# USBASP_M8535.net
KiCad netlist of a schematic drawn in EAGLE
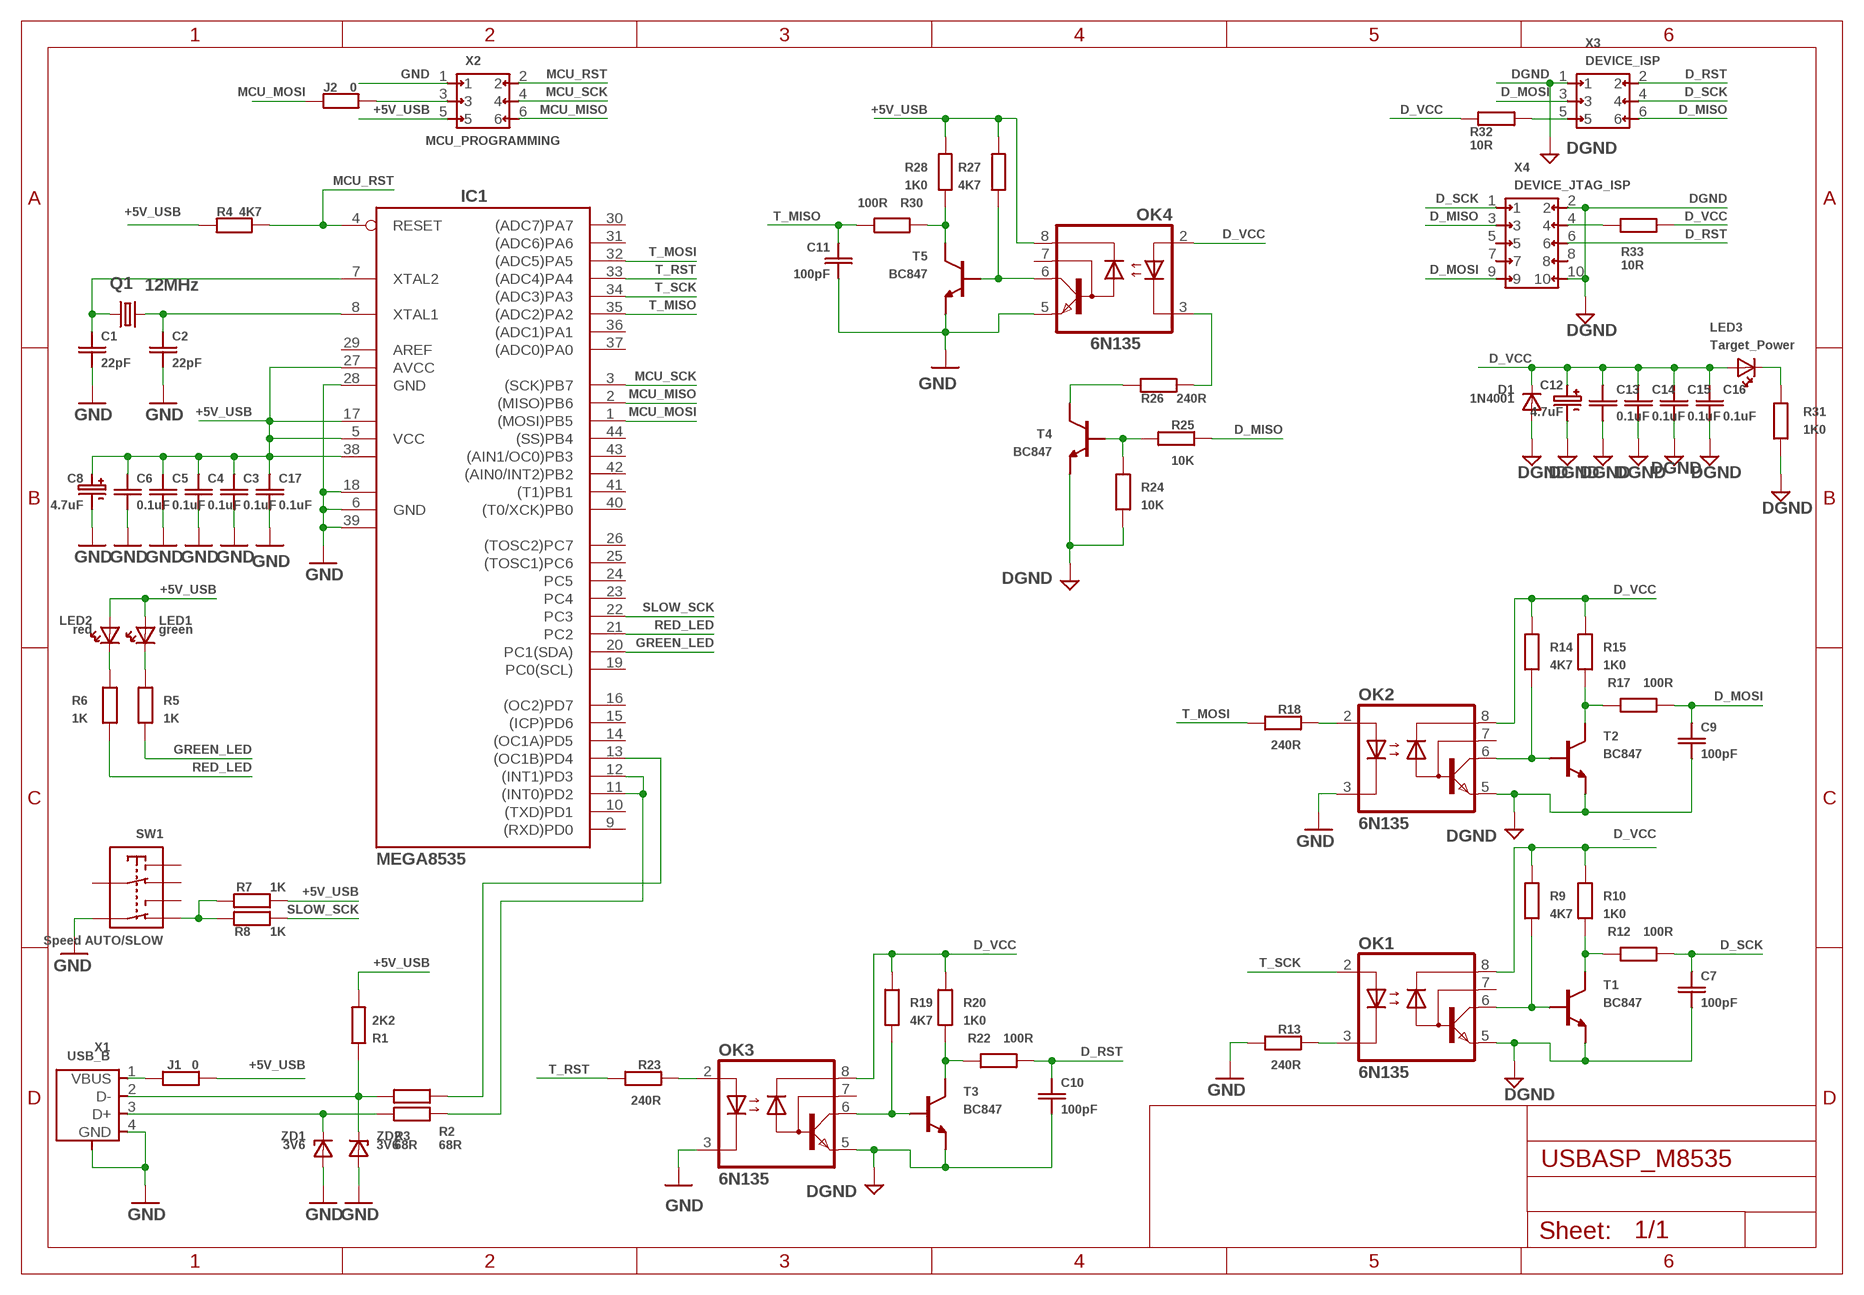
[diagram p0: schematic, sheet 1]

(export (version "E")
  (design (tool "Eeschema 10.0.6"))
  (components
    (comp (ref "C1")
      (value "22pF")
      (footprint "eagle-import:RSMD_0805")
      (libsource (lib "eagle-import") (part "CSMD_0805"))
    )
    (comp (ref "C2")
      (value "22pF")
      (footprint "eagle-import:RSMD_0805")
      (libsource (lib "eagle-import") (part "CSMD_0805"))
    )
    (comp (ref "C3")
      (value "0.1uF")
      (footprint "eagle-import:RSMD_0805")
      (libsource (lib "eagle-import") (part "CSMD_0805"))
    )
    (comp (ref "C4")
      (value "0.1uF")
      (footprint "eagle-import:RSMD_0805")
      (libsource (lib "eagle-import") (part "CSMD_0805"))
    )
    (comp (ref "C5")
      (value "0.1uF")
      (footprint "eagle-import:RSMD_0805")
      (libsource (lib "eagle-import") (part "CSMD_0805"))
    )
    (comp (ref "C6")
      (value "0.1uF")
      (footprint "eagle-import:RSMD_0805")
      (libsource (lib "eagle-import") (part "CSMD_0805"))
    )
    (comp (ref "C7")
      (value "100pF")
      (footprint "eagle-import:RSMD_0805")
      (libsource (lib "eagle-import") (part "CSMD_0805"))
    )
    (comp (ref "C8")
      (value "4.7uF")
      (footprint "eagle-import:CE_6.3MM")
      (libsource (lib "eagle-import") (part "CE6.3MM"))
    )
    (comp (ref "C9")
      (value "100pF")
      (footprint "eagle-import:RSMD_0805")
      (libsource (lib "eagle-import") (part "CSMD_0805"))
    )
    (comp (ref "C10")
      (value "100pF")
      (footprint "eagle-import:RSMD_0805")
      (libsource (lib "eagle-import") (part "CSMD_0805"))
    )
    (comp (ref "C11")
      (value "100pF")
      (footprint "eagle-import:RSMD_0805")
      (libsource (lib "eagle-import") (part "CSMD_0805"))
    )
    (comp (ref "C12")
      (value "4.7uF")
      (footprint "eagle-import:CE_6.3MM")
      (libsource (lib "eagle-import") (part "CE6.3MM"))
    )
    (comp (ref "C13")
      (value "0.1uF")
      (footprint "eagle-import:RSMD_0805")
      (libsource (lib "eagle-import") (part "CSMD_0805"))
    )
    (comp (ref "C14")
      (value "0.1uF")
      (footprint "eagle-import:RSMD_0805")
      (libsource (lib "eagle-import") (part "CSMD_0805"))
    )
    (comp (ref "C15")
      (value "0.1uF")
      (footprint "eagle-import:RSMD_0805")
      (libsource (lib "eagle-import") (part "CSMD_0805"))
    )
    (comp (ref "C16")
      (value "0.1uF")
      (footprint "eagle-import:RSMD_0805")
      (libsource (lib "eagle-import") (part "CSMD_0805"))
    )
    (comp (ref "C17")
      (value "0.1uF")
      (footprint "eagle-import:RSMD_0805")
      (libsource (lib "eagle-import") (part "CSMD_0805"))
    )
    (comp (ref "D1")
      (value "1N4001")
      (footprint "eagle-import:DO-41_10MM")
      (libsource (lib "eagle-import") (part "1N4001DO-41_10MM"))
    )
    (comp (ref "IC1")
      (value "MEGA8535")
      (footprint "eagle-import:TQFP44")
      (fields (field (name "MPN") "ATMEGA8535-16AU"))
      (libsource (lib "eagle-import") (part "MEGA8535-A"))
    )
    (comp (ref "J1")
      (value "0")
      (footprint "eagle-import:RSMD_1206")
      (libsource (lib "eagle-import") (part "RSMD_1206"))
    )
    (comp (ref "J2")
      (value "0")
      (footprint "eagle-import:RSMD_1206")
      (libsource (lib "eagle-import") (part "RSMD_1206"))
    )
    (comp (ref "LED1")
      (value "green")
      (footprint "eagle-import:LED3MM")
      (libsource (lib "eagle-import") (part "LED3MM"))
    )
    (comp (ref "LED2")
      (value "red")
      (footprint "eagle-import:LED3MM")
      (libsource (lib "eagle-import") (part "LED3MM"))
    )
    (comp (ref "LED3")
      (value "Target_Power")
      (footprint "eagle-import:LED3MM")
      (libsource (lib "eagle-import") (part "LED3MM"))
    )
    (comp (ref "OK1")
      (value "6N135")
      (footprint "eagle-import:DIL08")
      (fields (field (name "MF") "FAIRCHILD SEMICONDUCTOR"))
      (libsource (lib "eagle-import") (part "6N135"))
    )
    (comp (ref "OK2")
      (value "6N135")
      (footprint "eagle-import:DIL08")
      (fields (field (name "MF") "FAIRCHILD SEMICONDUCTOR"))
      (libsource (lib "eagle-import") (part "6N135"))
    )
    (comp (ref "OK3")
      (value "6N135")
      (footprint "eagle-import:DIL08")
      (fields (field (name "MF") "FAIRCHILD SEMICONDUCTOR"))
      (libsource (lib "eagle-import") (part "6N135"))
    )
    (comp (ref "OK4")
      (value "6N135")
      (footprint "eagle-import:DIL08")
      (fields (field (name "MF") "FAIRCHILD SEMICONDUCTOR"))
      (libsource (lib "eagle-import") (part "6N135"))
    )
    (comp (ref "Q1")
      (value "12MHz")
      (footprint "eagle-import:HC49U-V")
      (libsource (lib "eagle-import") (part "CRYSTALHC49U-V"))
    )
    (comp (ref "R1")
      (value "2K2")
      (footprint "eagle-import:RSMD_0805")
      (libsource (lib "eagle-import") (part "RSMD_0805"))
    )
    (comp (ref "R2")
      (value "68R")
      (footprint "eagle-import:RSMD_1206")
      (libsource (lib "eagle-import") (part "RSMD_1206"))
    )
    (comp (ref "R3")
      (value "68R")
      (footprint "eagle-import:RSMD_1206")
      (libsource (lib "eagle-import") (part "RSMD_1206"))
    )
    (comp (ref "R4")
      (value "4K7")
      (footprint "eagle-import:RSMD_0805")
      (libsource (lib "eagle-import") (part "RSMD_0805"))
    )
    (comp (ref "R5")
      (value "1K")
      (footprint "eagle-import:RSMD_0805")
      (libsource (lib "eagle-import") (part "RSMD_0805"))
    )
    (comp (ref "R6")
      (value "1K")
      (footprint "eagle-import:RSMD_0805")
      (libsource (lib "eagle-import") (part "RSMD_0805"))
    )
    (comp (ref "R7")
      (value "1K")
      (footprint "eagle-import:RSMD_0805")
      (libsource (lib "eagle-import") (part "RSMD_0805"))
    )
    (comp (ref "R8")
      (value "1K")
      (footprint "eagle-import:RSMD_1206")
      (libsource (lib "eagle-import") (part "RSMD_1206"))
    )
    (comp (ref "R9")
      (value "4K7")
      (footprint "eagle-import:RSMD_0805")
      (libsource (lib "eagle-import") (part "RSMD_0805"))
    )
    (comp (ref "R10")
      (value "1K0")
      (footprint "eagle-import:RSMD_0805")
      (libsource (lib "eagle-import") (part "RSMD_0805"))
    )
    (comp (ref "R12")
      (value "100R")
      (footprint "eagle-import:RSMD_0805")
      (libsource (lib "eagle-import") (part "RSMD_0805"))
    )
    (comp (ref "R13")
      (value "240R")
      (footprint "eagle-import:RSMD_0805")
      (libsource (lib "eagle-import") (part "RSMD_0805"))
    )
    (comp (ref "R14")
      (value "4K7")
      (footprint "eagle-import:RSMD_0805")
      (libsource (lib "eagle-import") (part "RSMD_0805"))
    )
    (comp (ref "R15")
      (value "1K0")
      (footprint "eagle-import:RSMD_0805")
      (libsource (lib "eagle-import") (part "RSMD_0805"))
    )
    (comp (ref "R17")
      (value "100R")
      (footprint "eagle-import:RSMD_0805")
      (libsource (lib "eagle-import") (part "RSMD_0805"))
    )
    (comp (ref "R18")
      (value "240R")
      (footprint "eagle-import:RSMD_0805")
      (libsource (lib "eagle-import") (part "RSMD_0805"))
    )
    (comp (ref "R19")
      (value "4K7")
      (footprint "eagle-import:RSMD_0805")
      (libsource (lib "eagle-import") (part "RSMD_0805"))
    )
    (comp (ref "R20")
      (value "1K0")
      (footprint "eagle-import:RSMD_0805")
      (libsource (lib "eagle-import") (part "RSMD_0805"))
    )
    (comp (ref "R22")
      (value "100R")
      (footprint "eagle-import:RSMD_0805")
      (libsource (lib "eagle-import") (part "RSMD_0805"))
    )
    (comp (ref "R23")
      (value "240R")
      (footprint "eagle-import:RSMD_0805")
      (libsource (lib "eagle-import") (part "RSMD_0805"))
    )
    (comp (ref "R24")
      (value "10K")
      (footprint "eagle-import:RSMD_0805")
      (libsource (lib "eagle-import") (part "RSMD_0805"))
    )
    (comp (ref "R25")
      (value "10K")
      (footprint "eagle-import:RSMD_0805")
      (libsource (lib "eagle-import") (part "RSMD_0805"))
    )
    (comp (ref "R26")
      (value "240R")
      (footprint "eagle-import:RSMD_0805")
      (libsource (lib "eagle-import") (part "RSMD_0805"))
    )
    (comp (ref "R27")
      (value "4K7")
      (footprint "eagle-import:RSMD_0805")
      (libsource (lib "eagle-import") (part "RSMD_0805"))
    )
    (comp (ref "R28")
      (value "1K0")
      (footprint "eagle-import:RSMD_0805")
      (libsource (lib "eagle-import") (part "RSMD_0805"))
    )
    (comp (ref "R30")
      (value "100R")
      (footprint "eagle-import:RSMD_0805")
      (libsource (lib "eagle-import") (part "RSMD_0805"))
    )
    (comp (ref "R31")
      (value "1K0")
      (footprint "eagle-import:RSMD_0805")
      (libsource (lib "eagle-import") (part "RSMD_0805"))
    )
    (comp (ref "R32")
      (value "10R")
      (footprint "eagle-import:R0207")
      (libsource (lib "eagle-import") (part "R0207"))
    )
    (comp (ref "R33")
      (value "10R")
      (footprint "eagle-import:R0207")
      (libsource (lib "eagle-import") (part "R0207"))
    )
    (comp (ref "SW1")
      (value "Speed AUTO/SLOW")
      (footprint "eagle-import:SWITCH_DOUBLE_2.54X4.0MM")
      (libsource (lib "eagle-import") (part "SWITCH_DOUBLE(2.54X4MM)"))
    )
    (comp (ref "T1")
      (value "BC847")
      (footprint "eagle-import:SOT23_SMALL_PADS")
      (libsource (lib "eagle-import") (part "BC847SOT23_SMALL_PADS"))
    )
    (comp (ref "T2")
      (value "BC847")
      (footprint "eagle-import:SOT23_SMALL_PADS")
      (libsource (lib "eagle-import") (part "BC847SOT23_SMALL_PADS"))
    )
    (comp (ref "T3")
      (value "BC847")
      (footprint "eagle-import:SOT23_SMALL_PADS")
      (libsource (lib "eagle-import") (part "BC847SOT23_SMALL_PADS"))
    )
    (comp (ref "T4")
      (value "BC847")
      (footprint "eagle-import:SOT23_SMALL_PADS")
      (libsource (lib "eagle-import") (part "BC847SOT23_SMALL_PADS"))
    )
    (comp (ref "T5")
      (value "BC847")
      (footprint "eagle-import:SOT23_SMALL_PADS")
      (libsource (lib "eagle-import") (part "BC847SOT23_SMALL_PADS"))
    )
    (comp (ref "X1")
      (value "USB_B")
      (footprint "eagle-import:USB_TYPE_B")
      (libsource (lib "eagle-import") (part "USB_TYPE_B(TYPE_B)"))
    )
    (comp (ref "X2")
      (value "MCU_PROGRAMMING")
      (footprint "eagle-import:PIN2X3_2.54MM")
      (libsource (lib "eagle-import") (part "PIN2X3_2.54MM"))
    )
    (comp (ref "X3")
      (value "DEVICE_ISP")
      (footprint "eagle-import:PIN2X3_2.54MM")
      (libsource (lib "eagle-import") (part "PIN2X3_2.54MM"))
    )
    (comp (ref "X4")
      (value "DEVICE_JTAG_ISP")
      (footprint "eagle-import:PIN2X5_2.54MM")
      (libsource (lib "eagle-import") (part "PIN2X5_2.54MM"))
    )
    (comp (ref "ZD1")
      (value "3V6")
      (footprint "eagle-import:SOD-80")
      (libsource (lib "eagle-import") (part "ZENNER(SOD_80)"))
    )
    (comp (ref "ZD2")
      (value "3V6")
      (footprint "eagle-import:SOD-80")
      (libsource (lib "eagle-import") (part "ZENNER(SOD_80)"))
    )
  )
  (nets
    (net (code "1") (name "/+5V_USB") (class "Default")
      (node (ref "C17") (pin "PAD_1") (pinfunction "PIN1_PAD_1") (pintype "bidirectional"))
      (node (ref "C3") (pin "PAD_1") (pinfunction "PIN1_PAD_1") (pintype "bidirectional"))
      (node (ref "C4") (pin "PAD_1") (pinfunction "PIN1_PAD_1") (pintype "bidirectional"))
      (node (ref "C5") (pin "PAD_1") (pinfunction "PIN1_PAD_1") (pintype "bidirectional"))
      (node (ref "C6") (pin "PAD_1") (pinfunction "PIN1_PAD_1") (pintype "bidirectional"))
      (node (ref "C8") (pin "+") (pinfunction "+_+") (pintype "bidirectional"))
      (node (ref "IC1") (pin "17") (pinfunction "VCC1_17") (pintype "power_in"))
      (node (ref "IC1") (pin "27") (pinfunction "AVCC_27") (pintype "power_in"))
      (node (ref "IC1") (pin "38") (pinfunction "VCC2_38") (pintype "power_in"))
      (node (ref "IC1") (pin "5") (pinfunction "VCC_5") (pintype "power_in"))
      (node (ref "J1") (pin "PAD_0") (pinfunction "PIN0_PAD_0") (pintype "passive"))
      (node (ref "LED1") (pin "ANODE") (pinfunction "ANODE_ANODE") (pintype "passive"))
      (node (ref "LED2") (pin "ANODE") (pinfunction "ANODE_ANODE") (pintype "passive"))
      (node (ref "OK4") (pin "8") (pinfunction "VCC_8") (pintype "passive"))
      (node (ref "R1") (pin "PAD_0") (pinfunction "PIN0_PAD_0") (pintype "passive"))
      (node (ref "R27") (pin "PAD_0") (pinfunction "PIN0_PAD_0") (pintype "passive"))
      (node (ref "R28") (pin "PAD_0") (pinfunction "PIN0_PAD_0") (pintype "passive"))
      (node (ref "R4") (pin "PAD_0") (pinfunction "PIN0_PAD_0") (pintype "passive"))
      (node (ref "R7") (pin "PAD_0") (pinfunction "PIN0_PAD_0") (pintype "passive"))
      (node (ref "X2") (pin "5") (pinfunction "5_5") (pintype "bidirectional"))
    )
    (net (code "2") (name "/D_MISO") (class "Default")
      (node (ref "R25") (pin "PAD_1") (pinfunction "PIN1_PAD_1") (pintype "passive"))
      (node (ref "X3") (pin "6") (pinfunction "6_6") (pintype "bidirectional"))
      (node (ref "X4") (pin "3") (pinfunction "3_3") (pintype "bidirectional"))
    )
    (net (code "3") (name "/D_MOSI") (class "Default")
      (node (ref "C9") (pin "PAD_1") (pinfunction "PIN1_PAD_1") (pintype "bidirectional"))
      (node (ref "R17") (pin "PAD_1") (pinfunction "PIN1_PAD_1") (pintype "passive"))
      (node (ref "X3") (pin "3") (pinfunction "3_3") (pintype "bidirectional"))
      (node (ref "X4") (pin "9") (pinfunction "9_9") (pintype "bidirectional"))
    )
    (net (code "4") (name "/D_RST") (class "Default")
      (node (ref "C10") (pin "PAD_1") (pinfunction "PIN1_PAD_1") (pintype "bidirectional"))
      (node (ref "R22") (pin "PAD_1") (pinfunction "PIN1_PAD_1") (pintype "passive"))
      (node (ref "X3") (pin "2") (pinfunction "2_2") (pintype "bidirectional"))
      (node (ref "X4") (pin "6") (pinfunction "6_6") (pintype "bidirectional"))
    )
    (net (code "5") (name "/D_SCK") (class "Default")
      (node (ref "C7") (pin "PAD_1") (pinfunction "PIN1_PAD_1") (pintype "bidirectional"))
      (node (ref "R12") (pin "PAD_1") (pinfunction "PIN1_PAD_1") (pintype "passive"))
      (node (ref "X3") (pin "4") (pinfunction "4_4") (pintype "bidirectional"))
      (node (ref "X4") (pin "1") (pinfunction "1_1") (pintype "bidirectional"))
    )
    (net (code "6") (name "/D_VCC") (class "Default")
      (node (ref "C12") (pin "+") (pinfunction "+_+") (pintype "bidirectional"))
      (node (ref "C13") (pin "PAD_1") (pinfunction "PIN1_PAD_1") (pintype "bidirectional"))
      (node (ref "C14") (pin "PAD_1") (pinfunction "PIN1_PAD_1") (pintype "bidirectional"))
      (node (ref "C15") (pin "PAD_1") (pinfunction "PIN1_PAD_1") (pintype "bidirectional"))
      (node (ref "C16") (pin "PAD_1") (pinfunction "PIN1_PAD_1") (pintype "bidirectional"))
      (node (ref "D1") (pin "CATHODE") (pinfunction "CATHODE_CATHODE") (pintype "passive"))
      (node (ref "LED3") (pin "ANODE") (pinfunction "ANODE_ANODE") (pintype "passive"))
      (node (ref "OK1") (pin "8") (pinfunction "VCC_8") (pintype "passive"))
      (node (ref "OK2") (pin "8") (pinfunction "VCC_8") (pintype "passive"))
      (node (ref "OK3") (pin "8") (pinfunction "VCC_8") (pintype "passive"))
      (node (ref "OK4") (pin "2") (pinfunction "A_2") (pintype "passive"))
      (node (ref "R10") (pin "PAD_0") (pinfunction "PIN0_PAD_0") (pintype "passive"))
      (node (ref "R14") (pin "PAD_0") (pinfunction "PIN0_PAD_0") (pintype "passive"))
      (node (ref "R15") (pin "PAD_0") (pinfunction "PIN0_PAD_0") (pintype "passive"))
      (node (ref "R19") (pin "PAD_0") (pinfunction "PIN0_PAD_0") (pintype "passive"))
      (node (ref "R20") (pin "PAD_0") (pinfunction "PIN0_PAD_0") (pintype "passive"))
      (node (ref "R32") (pin "PAD1") (pinfunction "PIN1_PAD1") (pintype "passive"))
      (node (ref "R33") (pin "PAD_0") (pinfunction "PIN0_PAD_0") (pintype "passive"))
      (node (ref "R9") (pin "PAD_0") (pinfunction "PIN0_PAD_0") (pintype "passive"))
    )
    (net (code "7") (name "/GREEN_LED") (class "Default")
      (node (ref "IC1") (pin "20") (pinfunction "PC1(SDA)_20") (pintype "bidirectional"))
      (node (ref "R5") (pin "PAD_1") (pinfunction "PIN1_PAD_1") (pintype "passive"))
    )
    (net (code "8") (name "/MCU_MISO") (class "Default")
      (node (ref "IC1") (pin "2") (pinfunction "(MISO)PB6_2") (pintype "bidirectional"))
      (node (ref "X2") (pin "6") (pinfunction "6_6") (pintype "bidirectional"))
    )
    (net (code "9") (name "/MCU_MOSI") (class "Default")
      (node (ref "IC1") (pin "1") (pinfunction "(MOSI)PB5_1") (pintype "bidirectional"))
      (node (ref "J2") (pin "PAD_0") (pinfunction "PIN0_PAD_0") (pintype "passive"))
    )
    (net (code "10") (name "/MCU_RST") (class "Default")
      (node (ref "IC1") (pin "4") (pinfunction "RESET_4") (pintype "input"))
      (node (ref "R4") (pin "PAD_1") (pinfunction "PIN1_PAD_1") (pintype "passive"))
      (node (ref "X2") (pin "2") (pinfunction "2_2") (pintype "bidirectional"))
    )
    (net (code "11") (name "/MCU_SCK") (class "Default")
      (node (ref "IC1") (pin "3") (pinfunction "(SCK)PB7_3") (pintype "bidirectional"))
      (node (ref "X2") (pin "4") (pinfunction "4_4") (pintype "bidirectional"))
    )
    (net (code "12") (name "/RED_LED") (class "Default")
      (node (ref "IC1") (pin "21") (pinfunction "PC2_21") (pintype "bidirectional"))
      (node (ref "R6") (pin "PAD_1") (pinfunction "PIN1_PAD_1") (pintype "passive"))
    )
    (net (code "13") (name "/SLOW_SCK") (class "Default")
      (node (ref "IC1") (pin "22") (pinfunction "PC3_22") (pintype "bidirectional"))
      (node (ref "R8") (pin "PAD_0") (pinfunction "PIN0_PAD_0") (pintype "passive"))
    )
    (net (code "14") (name "/T_MISO") (class "Default")
      (node (ref "C11") (pin "PAD_1") (pinfunction "PIN1_PAD_1") (pintype "bidirectional"))
      (node (ref "IC1") (pin "35") (pinfunction "(ADC2)PA2_35") (pintype "bidirectional"))
      (node (ref "R30") (pin "PAD_1") (pinfunction "PIN1_PAD_1") (pintype "passive"))
    )
    (net (code "15") (name "/T_MOSI") (class "Default")
      (node (ref "IC1") (pin "32") (pinfunction "(ADC5)PA5_32") (pintype "bidirectional"))
      (node (ref "R18") (pin "PAD_0") (pinfunction "PIN0_PAD_0") (pintype "passive"))
    )
    (net (code "16") (name "/T_RST") (class "Default")
      (node (ref "IC1") (pin "33") (pinfunction "(ADC4)PA4_33") (pintype "bidirectional"))
      (node (ref "R23") (pin "PAD_0") (pinfunction "PIN0_PAD_0") (pintype "passive"))
    )
    (net (code "17") (name "/T_SCK") (class "Default")
      (node (ref "IC1") (pin "34") (pinfunction "(ADC3)PA3_34") (pintype "bidirectional"))
      (node (ref "OK1") (pin "2") (pinfunction "A_2") (pintype "passive"))
    )
    (net (code "18") (name "DGND") (class "Default")
      (node (ref "C10") (pin "PAD_0") (pinfunction "PIN0_PAD_0") (pintype "bidirectional"))
      (node (ref "C12") (pin "-") (pinfunction "-_-") (pintype "bidirectional"))
      (node (ref "C13") (pin "PAD_0") (pinfunction "PIN0_PAD_0") (pintype "bidirectional"))
      (node (ref "C14") (pin "PAD_0") (pinfunction "PIN0_PAD_0") (pintype "bidirectional"))
      (node (ref "C15") (pin "PAD_0") (pinfunction "PIN0_PAD_0") (pintype "bidirectional"))
      (node (ref "C16") (pin "PAD_0") (pinfunction "PIN0_PAD_0") (pintype "bidirectional"))
      (node (ref "C7") (pin "PAD_0") (pinfunction "PIN0_PAD_0") (pintype "bidirectional"))
      (node (ref "C9") (pin "PAD_0") (pinfunction "PIN0_PAD_0") (pintype "bidirectional"))
      (node (ref "D1") (pin "ANODE") (pinfunction "ANODE_ANODE") (pintype "passive"))
      (node (ref "OK1") (pin "5") (pinfunction "GND_5") (pintype "passive"))
      (node (ref "OK2") (pin "5") (pinfunction "GND_5") (pintype "passive"))
      (node (ref "OK3") (pin "5") (pinfunction "GND_5") (pintype "passive"))
      (node (ref "R24") (pin "PAD_0") (pinfunction "PIN0_PAD_0") (pintype "passive"))
      (node (ref "R31") (pin "PAD_1") (pinfunction "PIN1_PAD_1") (pintype "passive"))
      (node (ref "T1") (pin "2") (pinfunction "E_2") (pintype "bidirectional"))
      (node (ref "T2") (pin "2") (pinfunction "E_2") (pintype "bidirectional"))
      (node (ref "T3") (pin "2") (pinfunction "E_2") (pintype "bidirectional"))
      (node (ref "T4") (pin "2") (pinfunction "E_2") (pintype "bidirectional"))
      (node (ref "X3") (pin "1") (pinfunction "1_1") (pintype "bidirectional"))
      (node (ref "X4") (pin "10") (pinfunction "10_10") (pintype "bidirectional"))
      (node (ref "X4") (pin "2") (pinfunction "2_2") (pintype "bidirectional"))
    )
    (net (code "19") (name "GND") (class "Default")
      (node (ref "C1") (pin "PAD_0") (pinfunction "PIN0_PAD_0") (pintype "bidirectional"))
      (node (ref "C11") (pin "PAD_0") (pinfunction "PIN0_PAD_0") (pintype "bidirectional"))
      (node (ref "C17") (pin "PAD_0") (pinfunction "PIN0_PAD_0") (pintype "bidirectional"))
      (node (ref "C2") (pin "PAD_0") (pinfunction "PIN0_PAD_0") (pintype "bidirectional"))
      (node (ref "C3") (pin "PAD_0") (pinfunction "PIN0_PAD_0") (pintype "bidirectional"))
      (node (ref "C4") (pin "PAD_0") (pinfunction "PIN0_PAD_0") (pintype "bidirectional"))
      (node (ref "C5") (pin "PAD_0") (pinfunction "PIN0_PAD_0") (pintype "bidirectional"))
      (node (ref "C6") (pin "PAD_0") (pinfunction "PIN0_PAD_0") (pintype "bidirectional"))
      (node (ref "C8") (pin "-") (pinfunction "-_-") (pintype "bidirectional"))
      (node (ref "IC1") (pin "18") (pinfunction "GND1_18") (pintype "power_in"))
      (node (ref "IC1") (pin "28") (pinfunction "GND_28") (pintype "power_in"))
      (node (ref "IC1") (pin "39") (pinfunction "GND2_39") (pintype "power_in"))
      (node (ref "IC1") (pin "6") (pinfunction "GND_6") (pintype "power_in"))
      (node (ref "OK2") (pin "3") (pinfunction "C_3") (pintype "passive"))
      (node (ref "OK3") (pin "3") (pinfunction "C_3") (pintype "passive"))
      (node (ref "OK4") (pin "5") (pinfunction "GND_5") (pintype "passive"))
      (node (ref "R13") (pin "PAD_0") (pinfunction "PIN0_PAD_0") (pintype "passive"))
      (node (ref "SW1") (pin "CENTER2") (pinfunction "CENTER2_CENTER2") (pintype "bidirectional"))
      (node (ref "T5") (pin "2") (pinfunction "E_2") (pintype "bidirectional"))
      (node (ref "X1") (pin "4") (pinfunction "GND_4") (pintype "bidirectional"))
      (node (ref "X1") (pin "PACKAGE_PAD1") (pinfunction "PACKAGE_PACKAGE_PAD1") (pintype "bidirectional"))
      (node (ref "X1") (pin "PACKAGE_PAD2") (pinfunction "PACKAGE_PACKAGE_PAD2") (pintype "bidirectional"))
      (node (ref "X2") (pin "1") (pinfunction "1_1") (pintype "bidirectional"))
      (node (ref "ZD1") (pin "ANODE") (pinfunction "ANODE_ANODE") (pintype "passive"))
      (node (ref "ZD2") (pin "ANODE") (pinfunction "ANODE_ANODE") (pintype "passive"))
    )
    (net (code "20") (name "Net-(C1-PIN1)") (class "Default")
      (node (ref "C1") (pin "PAD_1") (pinfunction "PIN1_PAD_1") (pintype "bidirectional"))
      (node (ref "IC1") (pin "7") (pinfunction "XTAL2_7") (pintype "bidirectional"))
      (node (ref "Q1") (pin "1") (pinfunction "1_1") (pintype "passive"))
    )
    (net (code "21") (name "Net-(C2-PIN1)") (class "Default")
      (node (ref "C2") (pin "PAD_1") (pinfunction "PIN1_PAD_1") (pintype "bidirectional"))
      (node (ref "IC1") (pin "8") (pinfunction "XTAL1_8") (pintype "bidirectional"))
      (node (ref "Q1") (pin "2") (pinfunction "2_2") (pintype "passive"))
    )
    (net (code "22") (name "Net-(IC1-(INT0)PD2)") (class "Default")
      (node (ref "IC1") (pin "11") (pinfunction "(INT0)PD2_11") (pintype "bidirectional"))
      (node (ref "IC1") (pin "12") (pinfunction "(INT1)PD3_12") (pintype "bidirectional"))
      (node (ref "R3") (pin "PAD_1") (pinfunction "PIN1_PAD_1") (pintype "passive"))
    )
    (net (code "23") (name "Net-(IC1-(OC1B)PD4)") (class "Default")
      (node (ref "IC1") (pin "13") (pinfunction "(OC1B)PD4_13") (pintype "bidirectional"))
      (node (ref "R2") (pin "PAD_0") (pinfunction "PIN0_PAD_0") (pintype "passive"))
    )
    (net (code "24") (name "Net-(J1-PIN1)") (class "Default")
      (node (ref "J1") (pin "PAD_1") (pinfunction "PIN1_PAD_1") (pintype "passive"))
      (node (ref "X1") (pin "1") (pinfunction "VBUS_1") (pintype "bidirectional"))
    )
    (net (code "25") (name "Net-(J2-PIN1)") (class "Default")
      (node (ref "J2") (pin "PAD_1") (pinfunction "PIN1_PAD_1") (pintype "passive"))
      (node (ref "X2") (pin "3") (pinfunction "3_3") (pintype "bidirectional"))
    )
    (net (code "26") (name "Net-(OK1-C)") (class "Default")
      (node (ref "OK1") (pin "3") (pinfunction "C_3") (pintype "passive"))
      (node (ref "R13") (pin "PAD_1") (pinfunction "PIN1_PAD_1") (pintype "passive"))
    )
    (net (code "27") (name "Net-(OK1-VO)") (class "Default")
      (node (ref "OK1") (pin "6") (pinfunction "VO_6") (pintype "passive"))
      (node (ref "R9") (pin "PAD_1") (pinfunction "PIN1_PAD_1") (pintype "passive"))
      (node (ref "T1") (pin "1") (pinfunction "B_1") (pintype "bidirectional"))
    )
    (net (code "28") (name "Net-(OK2-A)") (class "Default")
      (node (ref "OK2") (pin "2") (pinfunction "A_2") (pintype "passive"))
      (node (ref "R18") (pin "PAD_1") (pinfunction "PIN1_PAD_1") (pintype "passive"))
    )
    (net (code "29") (name "Net-(OK2-VO)") (class "Default")
      (node (ref "OK2") (pin "6") (pinfunction "VO_6") (pintype "passive"))
      (node (ref "R14") (pin "PAD_1") (pinfunction "PIN1_PAD_1") (pintype "passive"))
      (node (ref "T2") (pin "1") (pinfunction "B_1") (pintype "bidirectional"))
    )
    (net (code "30") (name "Net-(OK3-A)") (class "Default")
      (node (ref "OK3") (pin "2") (pinfunction "A_2") (pintype "passive"))
      (node (ref "R23") (pin "PAD_1") (pinfunction "PIN1_PAD_1") (pintype "passive"))
    )
    (net (code "31") (name "Net-(OK3-VO)") (class "Default")
      (node (ref "OK3") (pin "6") (pinfunction "VO_6") (pintype "passive"))
      (node (ref "R19") (pin "PAD_1") (pinfunction "PIN1_PAD_1") (pintype "passive"))
      (node (ref "T3") (pin "1") (pinfunction "B_1") (pintype "bidirectional"))
    )
    (net (code "32") (name "Net-(OK4-C)") (class "Default")
      (node (ref "OK4") (pin "3") (pinfunction "C_3") (pintype "passive"))
      (node (ref "R26") (pin "PAD_1") (pinfunction "PIN1_PAD_1") (pintype "passive"))
    )
    (net (code "33") (name "Net-(OK4-VO)") (class "Default")
      (node (ref "OK4") (pin "6") (pinfunction "VO_6") (pintype "passive"))
      (node (ref "R27") (pin "PAD_1") (pinfunction "PIN1_PAD_1") (pintype "passive"))
      (node (ref "T5") (pin "1") (pinfunction "B_1") (pintype "bidirectional"))
    )
    (net (code "34") (name "Net-(R1-PIN1)") (class "Default")
      (node (ref "R1") (pin "PAD_1") (pinfunction "PIN1_PAD_1") (pintype "passive"))
      (node (ref "R2") (pin "PAD_1") (pinfunction "PIN1_PAD_1") (pintype "passive"))
      (node (ref "X1") (pin "2") (pinfunction "D-_2") (pintype "bidirectional"))
      (node (ref "ZD2") (pin "CATHODE") (pinfunction "CATHODE_CATHODE") (pintype "passive"))
    )
    (net (code "35") (name "Net-(R3-PIN0)") (class "Default")
      (node (ref "R3") (pin "PAD_0") (pinfunction "PIN0_PAD_0") (pintype "passive"))
      (node (ref "X1") (pin "3") (pinfunction "D+_3") (pintype "bidirectional"))
      (node (ref "ZD1") (pin "CATHODE") (pinfunction "CATHODE_CATHODE") (pintype "passive"))
    )
    (net (code "36") (name "Net-(R5-PIN0)") (class "Default")
      (node (ref "LED1") (pin "CATHODE") (pinfunction "CATHODE_CATHODE") (pintype "passive"))
      (node (ref "R5") (pin "PAD_0") (pinfunction "PIN0_PAD_0") (pintype "passive"))
    )
    (net (code "37") (name "Net-(R6-PIN0)") (class "Default")
      (node (ref "LED2") (pin "CATHODE") (pinfunction "CATHODE_CATHODE") (pintype "passive"))
      (node (ref "R6") (pin "PAD_0") (pinfunction "PIN0_PAD_0") (pintype "passive"))
    )
    (net (code "38") (name "Net-(R7-PIN1)") (class "Default")
      (node (ref "R7") (pin "PAD_1") (pinfunction "PIN1_PAD_1") (pintype "passive"))
      (node (ref "R8") (pin "PAD_1") (pinfunction "PIN1_PAD_1") (pintype "passive"))
      (node (ref "SW1") (pin "POS_B2") (pinfunction "POS_B2_POS_B2") (pintype "bidirectional"))
    )
    (net (code "39") (name "Net-(R10-PIN1)") (class "Default")
      (node (ref "R10") (pin "PAD_1") (pinfunction "PIN1_PAD_1") (pintype "passive"))
      (node (ref "R12") (pin "PAD_0") (pinfunction "PIN0_PAD_0") (pintype "passive"))
      (node (ref "T1") (pin "3") (pinfunction "C_3") (pintype "bidirectional"))
    )
    (net (code "40") (name "Net-(R15-PIN1)") (class "Default")
      (node (ref "R15") (pin "PAD_1") (pinfunction "PIN1_PAD_1") (pintype "passive"))
      (node (ref "R17") (pin "PAD_0") (pinfunction "PIN0_PAD_0") (pintype "passive"))
      (node (ref "T2") (pin "3") (pinfunction "C_3") (pintype "bidirectional"))
    )
    (net (code "41") (name "Net-(R20-PIN1)") (class "Default")
      (node (ref "R20") (pin "PAD_1") (pinfunction "PIN1_PAD_1") (pintype "passive"))
      (node (ref "R22") (pin "PAD_0") (pinfunction "PIN0_PAD_0") (pintype "passive"))
      (node (ref "T3") (pin "3") (pinfunction "C_3") (pintype "bidirectional"))
    )
    (net (code "42") (name "Net-(R24-PIN1)") (class "Default")
      (node (ref "R24") (pin "PAD_1") (pinfunction "PIN1_PAD_1") (pintype "passive"))
      (node (ref "R25") (pin "PAD_0") (pinfunction "PIN0_PAD_0") (pintype "passive"))
      (node (ref "T4") (pin "1") (pinfunction "B_1") (pintype "bidirectional"))
    )
    (net (code "43") (name "Net-(R26-PIN0)") (class "Default")
      (node (ref "R26") (pin "PAD_0") (pinfunction "PIN0_PAD_0") (pintype "passive"))
      (node (ref "T4") (pin "3") (pinfunction "C_3") (pintype "bidirectional"))
    )
    (net (code "44") (name "Net-(R28-PIN1)") (class "Default")
      (node (ref "R28") (pin "PAD_1") (pinfunction "PIN1_PAD_1") (pintype "passive"))
      (node (ref "R30") (pin "PAD_0") (pinfunction "PIN0_PAD_0") (pintype "passive"))
      (node (ref "T5") (pin "3") (pinfunction "C_3") (pintype "bidirectional"))
    )
    (net (code "45") (name "Net-(R31-PIN0)") (class "Default")
      (node (ref "LED3") (pin "CATHODE") (pinfunction "CATHODE_CATHODE") (pintype "passive"))
      (node (ref "R31") (pin "PAD_0") (pinfunction "PIN0_PAD_0") (pintype "passive"))
    )
    (net (code "46") (name "Net-(R32-PIN0)") (class "Default")
      (node (ref "R32") (pin "PAD_0") (pinfunction "PIN0_PAD_0") (pintype "passive"))
      (node (ref "X3") (pin "5") (pinfunction "5_5") (pintype "bidirectional"))
    )
    (net (code "47") (name "Net-(R33-PIN1)") (class "Default")
      (node (ref "R33") (pin "PAD1") (pinfunction "PIN1_PAD1") (pintype "passive"))
      (node (ref "X4") (pin "4") (pinfunction "4_4") (pintype "bidirectional"))
    )
    (net (code "48") (name "unconnected-(IC1-(ADC0)PA0-Pad37)") (class "Default")
      (node (ref "IC1") (pin "37") (pinfunction "(ADC0)PA0_37") (pintype "bidirectional"))
    )
    (net (code "49") (name "unconnected-(IC1-(ADC1)PA1-Pad36)") (class "Default")
      (node (ref "IC1") (pin "36") (pinfunction "(ADC1)PA1_36") (pintype "bidirectional"))
    )
    (net (code "50") (name "unconnected-(IC1-(ADC6)PA6-Pad31)") (class "Default")
      (node (ref "IC1") (pin "31") (pinfunction "(ADC6)PA6_31") (pintype "bidirectional"))
    )
    (net (code "51") (name "unconnected-(IC1-(ADC7)PA7-Pad30)") (class "Default")
      (node (ref "IC1") (pin "30") (pinfunction "(ADC7)PA7_30") (pintype "bidirectional"))
    )
    (net (code "52") (name "unconnected-(IC1-(AIN0{slash}INT2)PB2-Pad42)") (class "Default")
      (node (ref "IC1") (pin "42") (pinfunction "(AIN0/INT2)PB2_42") (pintype "bidirectional"))
    )
    (net (code "53") (name "unconnected-(IC1-(AIN1{slash}OC0)PB3-Pad43)") (class "Default")
      (node (ref "IC1") (pin "43") (pinfunction "(AIN1/OC0)PB3_43") (pintype "bidirectional"))
    )
    (net (code "54") (name "unconnected-(IC1-(ICP)PD6-Pad15)") (class "Default")
      (node (ref "IC1") (pin "15") (pinfunction "(ICP)PD6_15") (pintype "bidirectional"))
    )
    (net (code "55") (name "unconnected-(IC1-(OC1A)PD5-Pad14)") (class "Default")
      (node (ref "IC1") (pin "14") (pinfunction "(OC1A)PD5_14") (pintype "bidirectional"))
    )
    (net (code "56") (name "unconnected-(IC1-(OC2)PD7-Pad16)") (class "Default")
      (node (ref "IC1") (pin "16") (pinfunction "(OC2)PD7_16") (pintype "bidirectional"))
    )
    (net (code "57") (name "unconnected-(IC1-(RXD)PD0-Pad9)") (class "Default")
      (node (ref "IC1") (pin "9") (pinfunction "(RXD)PD0_9") (pintype "bidirectional"))
    )
    (net (code "58") (name "unconnected-(IC1-(SS)PB4-Pad44)") (class "Default")
      (node (ref "IC1") (pin "44") (pinfunction "(SS)PB4_44") (pintype "bidirectional"))
    )
    (net (code "59") (name "unconnected-(IC1-(T0{slash}XCK)PB0-Pad40)") (class "Default")
      (node (ref "IC1") (pin "40") (pinfunction "(T0/XCK)PB0_40") (pintype "bidirectional"))
    )
    (net (code "60") (name "unconnected-(IC1-(T1)PB1-Pad41)") (class "Default")
      (node (ref "IC1") (pin "41") (pinfunction "(T1)PB1_41") (pintype "bidirectional"))
    )
    (net (code "61") (name "unconnected-(IC1-(TOSC1)PC6-Pad25)") (class "Default")
      (node (ref "IC1") (pin "25") (pinfunction "(TOSC1)PC6_25") (pintype "bidirectional"))
    )
    (net (code "62") (name "unconnected-(IC1-(TOSC2)PC7-Pad26)") (class "Default")
      (node (ref "IC1") (pin "26") (pinfunction "(TOSC2)PC7_26") (pintype "bidirectional"))
    )
    (net (code "63") (name "unconnected-(IC1-(TXD)PD1-Pad10)") (class "Default")
      (node (ref "IC1") (pin "10") (pinfunction "(TXD)PD1_10") (pintype "bidirectional"))
    )
    (net (code "64") (name "unconnected-(IC1-AREF-Pad29)") (class "Default")
      (node (ref "IC1") (pin "29") (pinfunction "AREF_29") (pintype "passive"))
    )
    (net (code "65") (name "unconnected-(IC1-PC0(SCL)-Pad19)") (class "Default")
      (node (ref "IC1") (pin "19") (pinfunction "PC0(SCL)_19") (pintype "bidirectional"))
    )
    (net (code "66") (name "unconnected-(IC1-PC4-Pad23)") (class "Default")
      (node (ref "IC1") (pin "23") (pinfunction "PC4_23") (pintype "bidirectional"))
    )
    (net (code "67") (name "unconnected-(IC1-PC5-Pad24)") (class "Default")
      (node (ref "IC1") (pin "24") (pinfunction "PC5_24") (pintype "bidirectional"))
    )
    (net (code "68") (name "unconnected-(OK1-VB-Pad7)") (class "Default")
      (node (ref "OK1") (pin "7") (pinfunction "VB_7") (pintype "passive"))
    )
    (net (code "69") (name "unconnected-(OK2-VB-Pad7)") (class "Default")
      (node (ref "OK2") (pin "7") (pinfunction "VB_7") (pintype "passive"))
    )
    (net (code "70") (name "unconnected-(OK3-VB-Pad7)") (class "Default")
      (node (ref "OK3") (pin "7") (pinfunction "VB_7") (pintype "passive"))
    )
    (net (code "71") (name "unconnected-(OK4-VB-Pad7)") (class "Default")
      (node (ref "OK4") (pin "7") (pinfunction "VB_7") (pintype "passive"))
    )
    (net (code "72") (name "unconnected-(SW1-PadCENTER1)") (class "Default")
      (node (ref "SW1") (pin "CENTER1") (pinfunction "CENTER1_CENTER1") (pintype "bidirectional"))
    )
    (net (code "73") (name "unconnected-(SW1-PadPOS_A1)") (class "Default")
      (node (ref "SW1") (pin "POS_A1") (pinfunction "POS_A1_POS_A1") (pintype "bidirectional"))
    )
    (net (code "74") (name "unconnected-(SW1-PadPOS_A2)") (class "Default")
      (node (ref "SW1") (pin "POS_A2") (pinfunction "POS_A2_POS_A2") (pintype "bidirectional"))
    )
    (net (code "75") (name "unconnected-(SW1-PadPOS_B1)") (class "Default")
      (node (ref "SW1") (pin "POS_B1") (pinfunction "POS_B1_POS_B1") (pintype "bidirectional"))
    )
    (net (code "76") (name "unconnected-(X4-Pad5)") (class "Default")
      (node (ref "X4") (pin "5") (pinfunction "5_5") (pintype "bidirectional"))
    )
    (net (code "77") (name "unconnected-(X4-Pad7)") (class "Default")
      (node (ref "X4") (pin "7") (pinfunction "7_7") (pintype "bidirectional"))
    )
    (net (code "78") (name "unconnected-(X4-Pad8)") (class "Default")
      (node (ref "X4") (pin "8") (pinfunction "8_8") (pintype "bidirectional"))
    )
  )
)
